# LM2941_Variable_Regulator_5VDC-10VDC.net
KiCad netlist of a schematic drawn in EAGLE
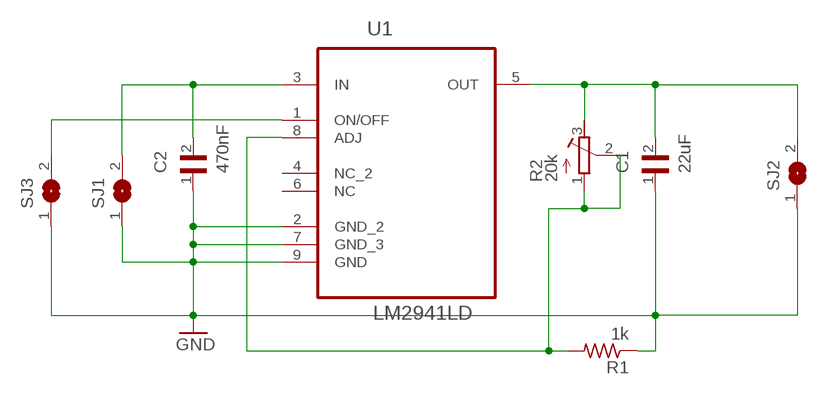
[diagram p0: schematic, sheet 1]

(export (version "E")
  (design (tool "Eeschema 10.0.6"))
  (components
    (comp (ref "C1")
      (value "22uF")
      (footprint "eagle-import:CAPC6153X390N")
      (fields (field (name "MF") "Murata") (field (name "MP") "KCM55QR7YA226KH01L"))
      (libsource (lib "eagle-import") (part "KCM55QR7YA226KH01L"))
    )
    (comp (ref "C2")
      (value "470nF")
      (footprint "eagle-import:CAPC1608X90N")
      (fields (field (name "MF") "Murata") (field (name "MP") "GRM188R7YA474KE05D"))
      (libsource (lib "eagle-import") (part "GRM188R7YA474KE05D"))
    )
    (comp (ref "R1")
      (value "1k")
      (footprint "eagle-import:R0805")
      (libsource (lib "eagle-import") (part "R-US_R0805"))
    )
    (comp (ref "R2")
      (value "20k")
      (footprint "eagle-import:RTRIM3214W")
      (libsource (lib "eagle-import") (part "R-TRIMM3214W"))
    )
    (comp (ref "SJ1")
      (value "SJW")
      (footprint "eagle-import:SJW")
      (libsource (lib "eagle-import") (part "SJW"))
    )
    (comp (ref "SJ2")
      (value "SJW")
      (footprint "eagle-import:SJW")
      (libsource (lib "eagle-import") (part "SJW"))
    )
    (comp (ref "SJ3")
      (value "SJW")
      (footprint "eagle-import:SJW")
      (libsource (lib "eagle-import") (part "SJW"))
    )
    (comp (ref "U1")
      (value "LM2941LD")
      (footprint "eagle-import:DFN400X400X80-9N")
      (fields (field (name "MF") "Texas Instruments"))
      (libsource (lib "eagle-import") (part "LM2941LD"))
    )
  )
  (nets
    (net (code "1") (name "GND") (class "Default")
      (node (ref "C1") (pin "1") (pinfunction "1_1") (pintype "passive"))
      (node (ref "C2") (pin "1") (pinfunction "1_1") (pintype "passive"))
      (node (ref "R1") (pin "1") (pinfunction "1_1") (pintype "passive"))
      (node (ref "SJ1") (pin "1") (pinfunction "1_1") (pintype "passive"))
      (node (ref "SJ2") (pin "1") (pinfunction "1_1") (pintype "passive"))
      (node (ref "SJ3") (pin "1") (pinfunction "1_1") (pintype "passive"))
      (node (ref "U1") (pin "2") (pinfunction "GND_2_2") (pintype "passive"))
      (node (ref "U1") (pin "7") (pinfunction "GND_3_7") (pintype "passive"))
      (node (ref "U1") (pin "9") (pinfunction "GND_9") (pintype "passive"))
    )
    (net (code "2") (name "Net-(R2-A)") (class "Default")
      (node (ref "R1") (pin "2") (pinfunction "2_2") (pintype "passive"))
      (node (ref "R2") (pin "1") (pinfunction "A_1") (pintype "passive"))
      (node (ref "R2") (pin "2") (pinfunction "S_2") (pintype "passive"))
      (node (ref "U1") (pin "8") (pinfunction "ADJ_8") (pintype "passive"))
    )
    (net (code "3") (name "Net-(R2-E)") (class "Default")
      (node (ref "C1") (pin "2") (pinfunction "2_2") (pintype "passive"))
      (node (ref "R2") (pin "3") (pinfunction "E_3") (pintype "passive"))
      (node (ref "SJ2") (pin "2") (pinfunction "2_2") (pintype "passive"))
      (node (ref "U1") (pin "5") (pinfunction "OUT_5") (pintype "output"))
    )
    (net (code "4") (name "Net-(U1-IN)") (class "Default")
      (node (ref "C2") (pin "2") (pinfunction "2_2") (pintype "passive"))
      (node (ref "SJ1") (pin "2") (pinfunction "2_2") (pintype "passive"))
      (node (ref "U1") (pin "3") (pinfunction "IN_3") (pintype "input"))
    )
    (net (code "5") (name "Net-(U1-ON{slash}OFF)") (class "Default")
      (node (ref "SJ3") (pin "2") (pinfunction "2_2") (pintype "passive"))
      (node (ref "U1") (pin "1") (pinfunction "ON/OFF_1") (pintype "passive"))
    )
    (net (code "6") (name "unconnected-(U1-NC-Pad6)") (class "Default")
      (node (ref "U1") (pin "6") (pinfunction "NC_6") (pintype "no_connect"))
    )
    (net (code "7") (name "unconnected-(U1-NC_2-Pad4)") (class "Default")
      (node (ref "U1") (pin "4") (pinfunction "NC_2_4") (pintype "no_connect"))
    )
  )
)
